# Photon_Pixel_Shield_v6_no_diode.net
KiCad netlist of a schematic drawn in EAGLE
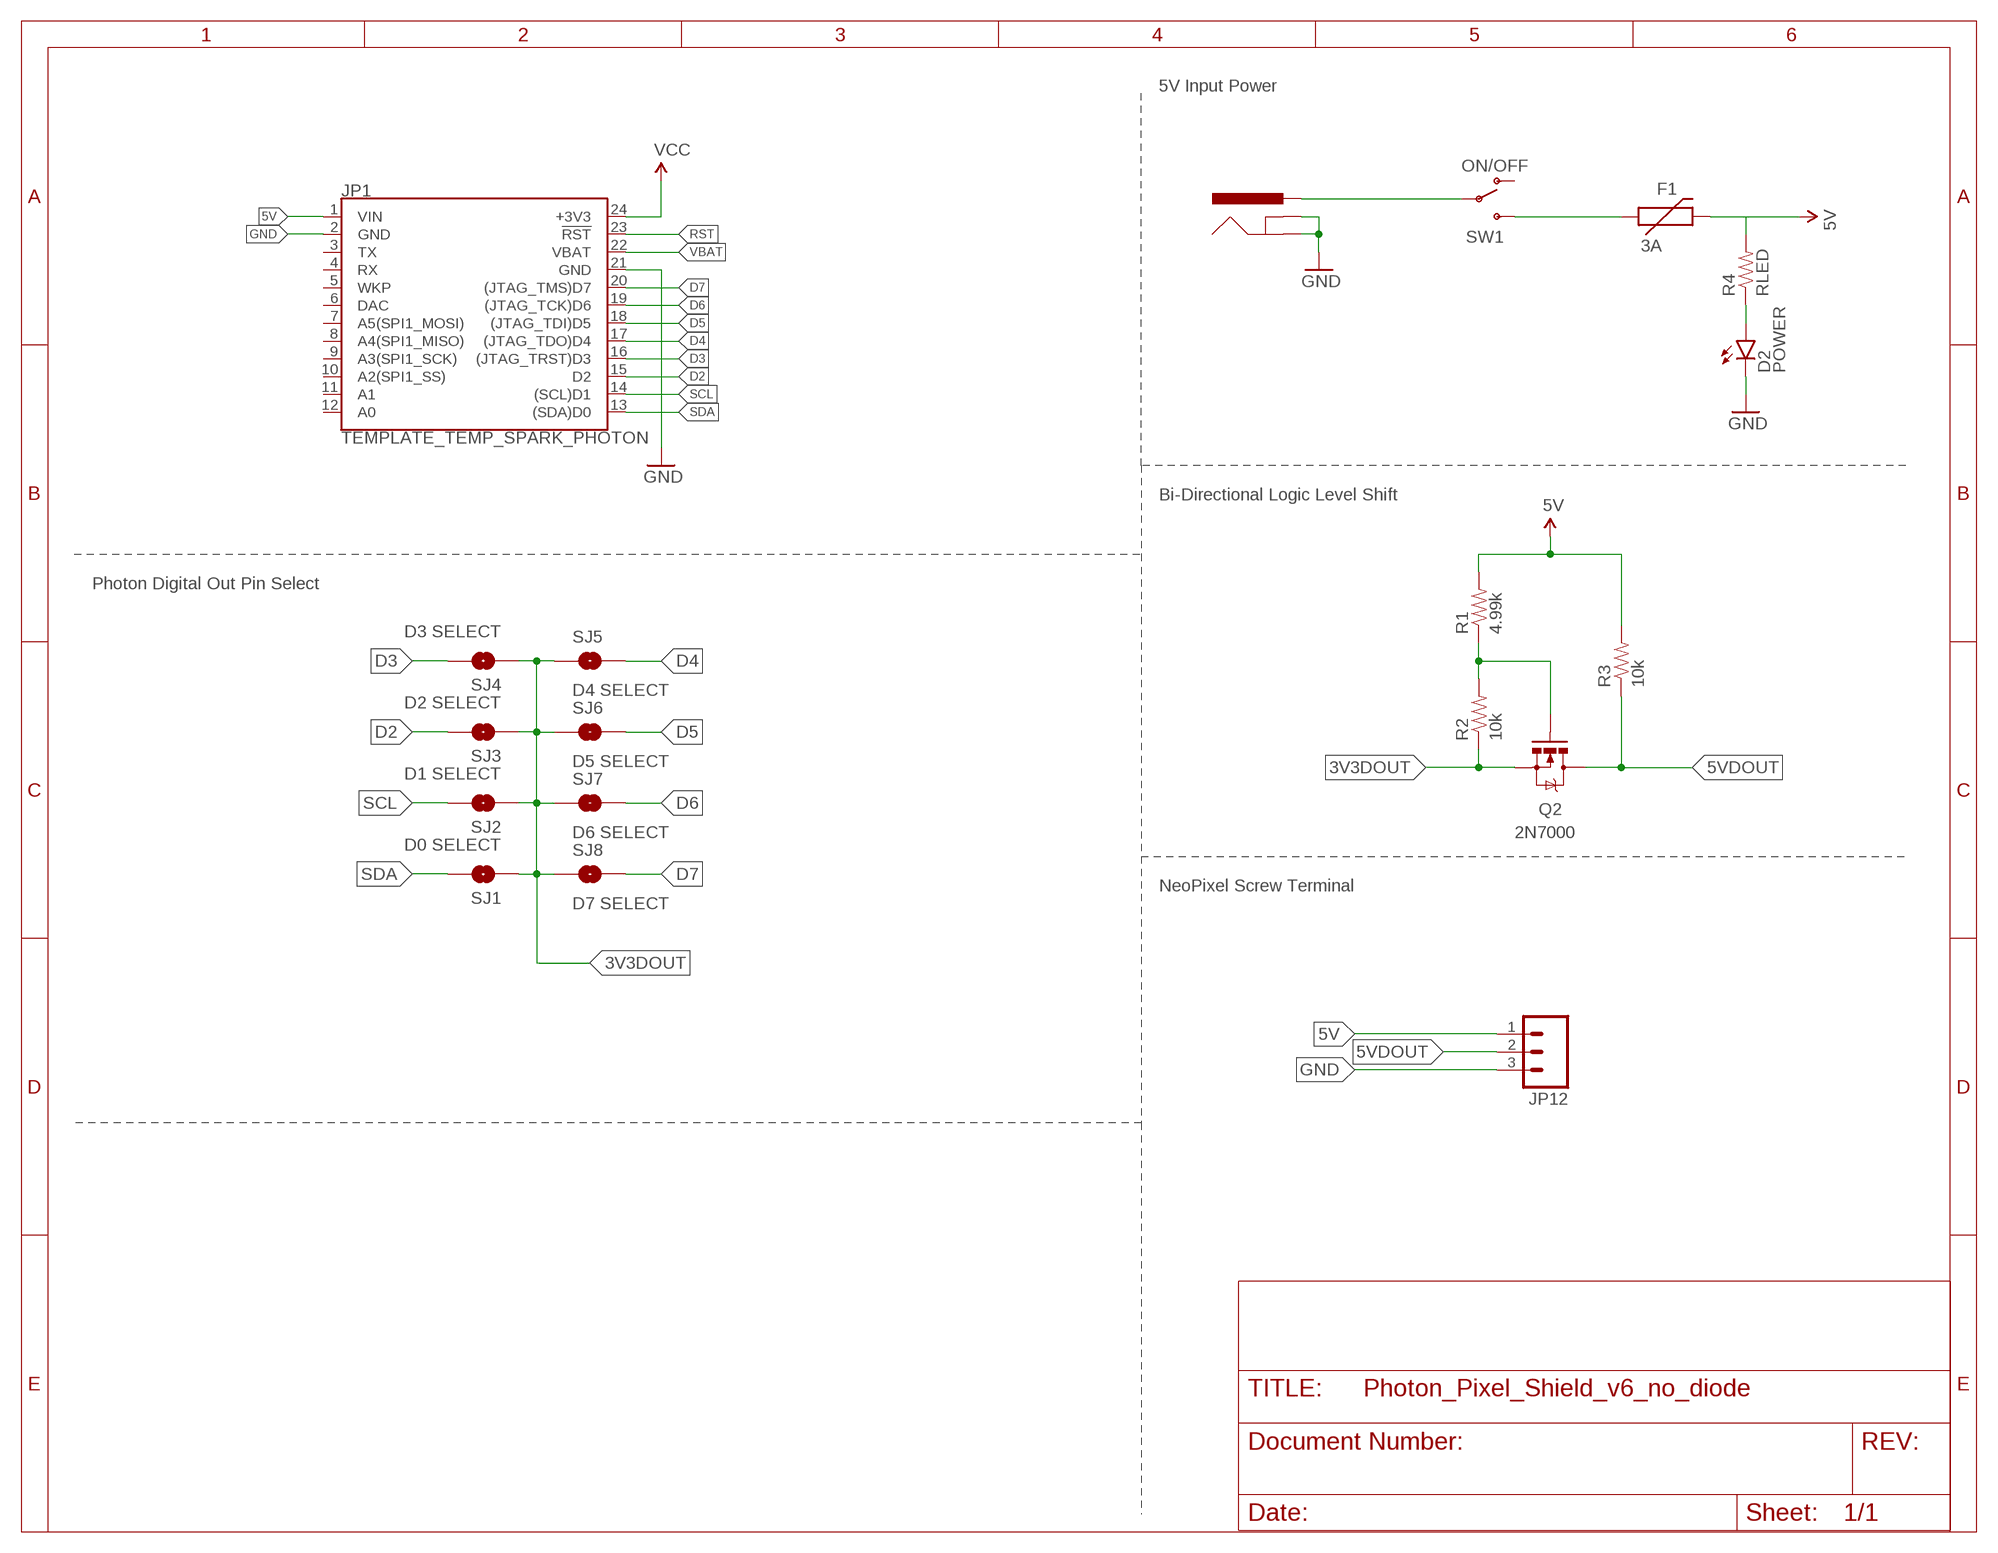
[diagram p0: schematic, sheet 1]

(export (version "E")
  (design (tool "Eeschema 10.0.6"))
  (components
    (comp (ref "D2")
      (value "POWER")
      (footprint "eagle-import:LED3MM")
      (libsource (lib "eagle-import") (part "LED3MM"))
    )
    (comp (ref "F1")
      (value "3A")
      (footprint "eagle-import:PTC")
      (libsource (lib "eagle-import") (part "PTCPTH"))
    )
    (comp (ref "J1")
      (value "POWER_JACKPTH")
      (footprint "eagle-import:POWER_JACK_PTH")
      (libsource (lib "eagle-import") (part "POWER_JACKPTH"))
    )
    (comp (ref "JP1")
      (value "TEMPLATE_TEMP_SPARK_PHOTON")
      (footprint "eagle-import:TEMPLATE_TEMP_SPARK_PHOTON")
      (libsource (lib "eagle-import") (part "TEMPLATE_TEMP_SPARK_PHOTON"))
    )
    (comp (ref "JP12")
      (value "M03SCREW")
      (footprint "eagle-import:SCREWTERMINAL-3.5MM-3")
      (libsource (lib "eagle-import") (part "M03SCREW"))
    )
    (comp (ref "Q2")
      (value "2N7000")
      (footprint "eagle-import:TO-92")
      (libsource (lib "eagle-import") (part "MOSFET-NCHANNEL2N7000"))
    )
    (comp (ref "R1")
      (value "4.99k")
      (footprint "eagle-import:AXIAL-0.3")
      (libsource (lib "eagle-import") (part "10KOHM-1/4W-1%(PTH)HORIZ"))
    )
    (comp (ref "R2")
      (value "10k")
      (footprint "eagle-import:AXIAL-0.3")
      (libsource (lib "eagle-import") (part "10KOHM-1/4W-1%(PTH)HORIZ"))
    )
    (comp (ref "R3")
      (value "10k")
      (footprint "eagle-import:AXIAL-0.3")
      (libsource (lib "eagle-import") (part "10KOHM-1/4W-1%(PTH)HORIZ"))
    )
    (comp (ref "R4")
      (value "RLED")
      (footprint "eagle-import:AXIAL-0.3")
      (libsource (lib "eagle-import") (part "10KOHM-1/4W-1%(PTH)HORIZ"))
    )
    (comp (ref "SJ1")
      (value "D0 SELECT")
      (footprint "eagle-import:SJ_2S-NO")
      (libsource (lib "eagle-import") (part "SOLDERJUMPERNO"))
    )
    (comp (ref "SJ2")
      (value "D1 SELECT")
      (footprint "eagle-import:SJ_2S-NO")
      (libsource (lib "eagle-import") (part "SOLDERJUMPERNO"))
    )
    (comp (ref "SJ3")
      (value "D2 SELECT")
      (footprint "eagle-import:SJ_2S-NO")
      (libsource (lib "eagle-import") (part "SOLDERJUMPERNO"))
    )
    (comp (ref "SJ4")
      (value "D3 SELECT")
      (footprint "eagle-import:SJ_2S-NO")
      (libsource (lib "eagle-import") (part "SOLDERJUMPERNO"))
    )
    (comp (ref "SJ5")
      (value "D4 SELECT")
      (footprint "eagle-import:SJ_2S-NO")
      (libsource (lib "eagle-import") (part "SOLDERJUMPERNO"))
    )
    (comp (ref "SJ6")
      (value "D5 SELECT")
      (footprint "eagle-import:SJ_2S-NO")
      (libsource (lib "eagle-import") (part "SOLDERJUMPERNO"))
    )
    (comp (ref "SJ7")
      (value "D6 SELECT")
      (footprint "eagle-import:SJ_2S-NO")
      (libsource (lib "eagle-import") (part "SOLDERJUMPERNO"))
    )
    (comp (ref "SJ8")
      (value "D7 SELECT")
      (footprint "eagle-import:SJ_2S-NO")
      (libsource (lib "eagle-import") (part "SOLDERJUMPERNO"))
    )
    (comp (ref "SW1")
      (value "ON/OFF")
      (footprint "eagle-import:SWITCH-SPST")
      (libsource (lib "eagle-import") (part "SWITCH-SPSTPTH"))
    )
  )
  (nets
    (net (code "1") (name "3V3DOUT") (class "Default")
      (node (ref "Q2") (pin "1") (pinfunction "S_1") (pintype "passive"))
      (node (ref "R2") (pin "P$1") (pinfunction "1_P$1") (pintype "passive"))
      (node (ref "SJ1") (pin "1") (pinfunction "1_1") (pintype "passive"))
      (node (ref "SJ2") (pin "1") (pinfunction "1_1") (pintype "passive"))
      (node (ref "SJ3") (pin "1") (pinfunction "1_1") (pintype "passive"))
      (node (ref "SJ4") (pin "1") (pinfunction "1_1") (pintype "passive"))
      (node (ref "SJ5") (pin "1") (pinfunction "1_1") (pintype "passive"))
      (node (ref "SJ6") (pin "1") (pinfunction "1_1") (pintype "passive"))
      (node (ref "SJ7") (pin "1") (pinfunction "1_1") (pintype "passive"))
      (node (ref "SJ8") (pin "1") (pinfunction "1_1") (pintype "passive"))
    )
    (net (code "2") (name "5V") (class "Default")
      (node (ref "F1") (pin "P$2") (pinfunction "2_P$2") (pintype "bidirectional"))
      (node (ref "JP1") (pin "1") (pinfunction "VIN_1") (pintype "bidirectional"))
      (node (ref "JP12") (pin "1") (pinfunction "1_1") (pintype "passive"))
      (node (ref "R1") (pin "P$2") (pinfunction "2_P$2") (pintype "passive"))
      (node (ref "R3") (pin "P$2") (pinfunction "2_P$2") (pintype "passive"))
      (node (ref "R4") (pin "P$2") (pinfunction "2_P$2") (pintype "passive"))
    )
    (net (code "3") (name "5VDOUT") (class "Default")
      (node (ref "JP12") (pin "2") (pinfunction "2_2") (pintype "passive"))
      (node (ref "Q2") (pin "3") (pinfunction "D_3") (pintype "passive"))
      (node (ref "R3") (pin "P$1") (pinfunction "1_P$1") (pintype "passive"))
    )
    (net (code "4") (name "D2") (class "Default")
      (node (ref "JP1") (pin "15") (pinfunction "D2_15") (pintype "bidirectional"))
      (node (ref "SJ3") (pin "2") (pinfunction "2_2") (pintype "passive"))
    )
    (net (code "5") (name "D3") (class "Default")
      (node (ref "JP1") (pin "16") (pinfunction "(JTAG_TRST)D3_16") (pintype "bidirectional"))
      (node (ref "SJ4") (pin "2") (pinfunction "2_2") (pintype "passive"))
    )
    (net (code "6") (name "D4") (class "Default")
      (node (ref "JP1") (pin "17") (pinfunction "(JTAG_TDO)D4_17") (pintype "bidirectional"))
      (node (ref "SJ5") (pin "2") (pinfunction "2_2") (pintype "passive"))
    )
    (net (code "7") (name "D5") (class "Default")
      (node (ref "JP1") (pin "18") (pinfunction "(JTAG_TDI)D5_18") (pintype "bidirectional"))
      (node (ref "SJ6") (pin "2") (pinfunction "2_2") (pintype "passive"))
    )
    (net (code "8") (name "D6") (class "Default")
      (node (ref "JP1") (pin "19") (pinfunction "(JTAG_TCK)D6_19") (pintype "bidirectional"))
      (node (ref "SJ7") (pin "2") (pinfunction "2_2") (pintype "passive"))
    )
    (net (code "9") (name "D7") (class "Default")
      (node (ref "JP1") (pin "20") (pinfunction "(JTAG_TMS)D7_20") (pintype "bidirectional"))
      (node (ref "SJ8") (pin "2") (pinfunction "2_2") (pintype "passive"))
    )
    (net (code "10") (name "GND") (class "Default")
      (node (ref "D2") (pin "K") (pinfunction "C_K") (pintype "passive"))
      (node (ref "J1") (pin "GND") (pinfunction "GND_GND") (pintype "bidirectional"))
      (node (ref "J1") (pin "GNDBREAK") (pinfunction "GNDBREAK_GNDBREAK") (pintype "bidirectional"))
      (node (ref "JP1") (pin "2") (pinfunction "GND_2") (pintype "bidirectional"))
      (node (ref "JP1") (pin "21") (pinfunction "GND_21") (pintype "bidirectional"))
      (node (ref "JP12") (pin "3") (pinfunction "3_3") (pintype "passive"))
    )
    (net (code "11") (name "Net-(F1-1)") (class "Default")
      (node (ref "F1") (pin "P$1") (pinfunction "1_P$1") (pintype "bidirectional"))
      (node (ref "SW1") (pin "3") (pinfunction "S_3") (pintype "passive"))
    )
    (net (code "12") (name "Net-(Q2-G)") (class "Default")
      (node (ref "Q2") (pin "2") (pinfunction "G_2") (pintype "passive"))
      (node (ref "R1") (pin "P$1") (pinfunction "1_P$1") (pintype "passive"))
      (node (ref "R2") (pin "P$2") (pinfunction "2_P$2") (pintype "passive"))
    )
    (net (code "13") (name "Net-(R4-1)") (class "Default")
      (node (ref "D2") (pin "A") (pinfunction "A_A") (pintype "passive"))
      (node (ref "R4") (pin "P$1") (pinfunction "1_P$1") (pintype "passive"))
    )
    (net (code "14") (name "Net-(SW1-P)") (class "Default")
      (node (ref "J1") (pin "PWR") (pinfunction "PWR_PWR") (pintype "bidirectional"))
      (node (ref "SW1") (pin "2") (pinfunction "P_2") (pintype "passive"))
    )
    (net (code "15") (name "RST") (class "Default")
      (node (ref "JP1") (pin "23") (pinfunction "~{RST}_23") (pintype "bidirectional"))
    )
    (net (code "16") (name "SCL") (class "Default")
      (node (ref "JP1") (pin "14") (pinfunction "(SCL)D1_14") (pintype "bidirectional"))
      (node (ref "SJ2") (pin "2") (pinfunction "2_2") (pintype "passive"))
    )
    (net (code "17") (name "SDA") (class "Default")
      (node (ref "JP1") (pin "13") (pinfunction "(SDA)D0_13") (pintype "bidirectional"))
      (node (ref "SJ1") (pin "2") (pinfunction "2_2") (pintype "passive"))
    )
    (net (code "18") (name "VBAT") (class "Default")
      (node (ref "JP1") (pin "22") (pinfunction "VBAT_22") (pintype "bidirectional"))
    )
    (net (code "19") (name "VCC") (class "Default")
      (node (ref "JP1") (pin "24") (pinfunction "+3V3_24") (pintype "bidirectional"))
    )
    (net (code "20") (name "unconnected-(JP1-A0-Pad12)") (class "Default")
      (node (ref "JP1") (pin "12") (pinfunction "A0_12") (pintype "bidirectional"))
    )
    (net (code "21") (name "unconnected-(JP1-A1-Pad11)") (class "Default")
      (node (ref "JP1") (pin "11") (pinfunction "A1_11") (pintype "bidirectional"))
    )
    (net (code "22") (name "unconnected-(JP1-A2(SPI1_SS)-Pad10)") (class "Default")
      (node (ref "JP1") (pin "10") (pinfunction "A2(SPI1_SS)_10") (pintype "bidirectional"))
    )
    (net (code "23") (name "unconnected-(JP1-A3(SPI1_SCK)-Pad9)") (class "Default")
      (node (ref "JP1") (pin "9") (pinfunction "A3(SPI1_SCK)_9") (pintype "bidirectional"))
    )
    (net (code "24") (name "unconnected-(JP1-A4(SPI1_MISO)-Pad8)") (class "Default")
      (node (ref "JP1") (pin "8") (pinfunction "A4(SPI1_MISO)_8") (pintype "bidirectional"))
    )
    (net (code "25") (name "unconnected-(JP1-A5(SPI1_MOSI)-Pad7)") (class "Default")
      (node (ref "JP1") (pin "7") (pinfunction "A5(SPI1_MOSI)_7") (pintype "bidirectional"))
    )
    (net (code "26") (name "unconnected-(JP1-DAC-Pad6)") (class "Default")
      (node (ref "JP1") (pin "6") (pinfunction "DAC_6") (pintype "bidirectional"))
    )
    (net (code "27") (name "unconnected-(JP1-RX-Pad4)") (class "Default")
      (node (ref "JP1") (pin "4") (pinfunction "RX_4") (pintype "bidirectional"))
    )
    (net (code "28") (name "unconnected-(JP1-TX-Pad3)") (class "Default")
      (node (ref "JP1") (pin "3") (pinfunction "TX_3") (pintype "bidirectional"))
    )
    (net (code "29") (name "unconnected-(JP1-WKP-Pad5)") (class "Default")
      (node (ref "JP1") (pin "5") (pinfunction "WKP_5") (pintype "bidirectional"))
    )
    (net (code "30") (name "unconnected-(SW1-O-Pad1)") (class "Default")
      (node (ref "SW1") (pin "1") (pinfunction "O_1") (pintype "passive"))
    )
  )
)
